# BNO085_IMU.net
KiCad netlist of a schematic drawn in Altium Designer
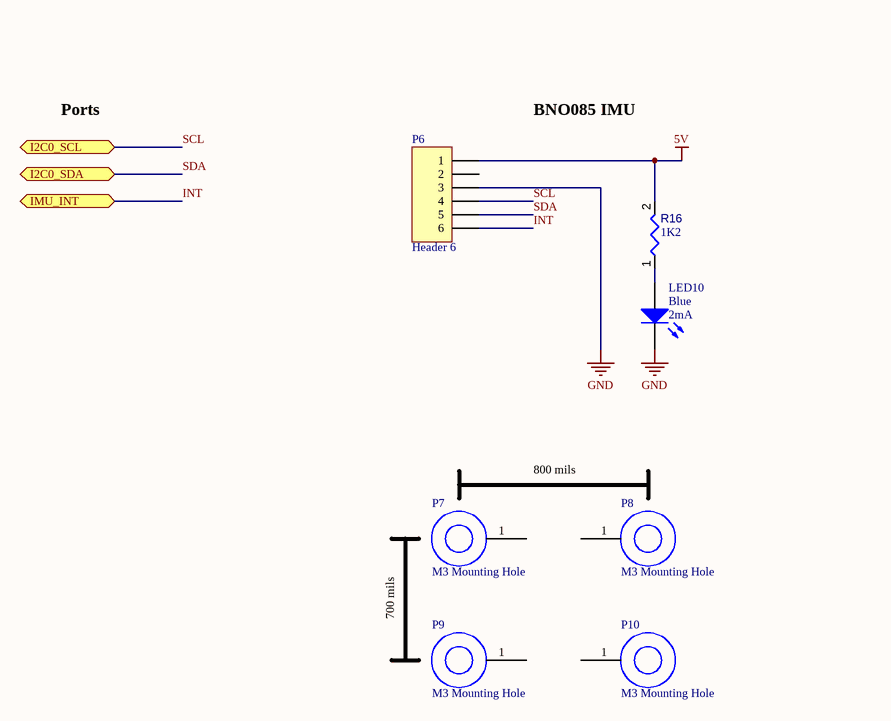
[diagram p0: BNO085_IMU.SchDoc]

(export (version "E")
  (design (tool "Eeschema 10.0.6"))
  (components
    (comp (ref "LED10")
      (value "Blue")
      (footprint "1206_A")
      (description "KPT-3216LVVBC-D -  LED, 3.2mm x 1.6mm, Blue, SMD, 2 mA, 2.65 V, 470 nm")
      (fields
        (field (name "MANUFACTURER") "Kingbright")
        (field (name "PARTNUMBER") "KPT-3216LVVBC-D")
        (field (name "IF") "2mA")
      )
      (libsource (lib "Altium Content Vault") (part "CMP-1426-00015-1"))
    )
    (comp (ref "P6")
      (value "Header 6")
      (footprint "HDR1X6")
      (description "Header, 6-Pin")
      (fields (field (name "PUBLISHER") "Altium Limited"))
      (libsource (lib "Miscellaneous Connectors") (part "Header 6"))
    )
    (comp (ref "P7")
      (value "M3 Mounting Hole")
      (footprint "M3 Mounting Hole")
      (description "M3 Mounting Hole, ID 2.73mm")
      (libsource (lib "CC3501_Misc_Symbols") (part "M3 Mounting Hole"))
    )
    (comp (ref "P8")
      (value "M3 Mounting Hole")
      (footprint "M3 Mounting Hole")
      (description "M3 Mounting Hole, ID 2.73mm")
      (libsource (lib "CC3501_Misc_Symbols") (part "M3 Mounting Hole"))
    )
    (comp (ref "P9")
      (value "M3 Mounting Hole")
      (footprint "M3 Mounting Hole")
      (description "M3 Mounting Hole, ID 2.73mm")
      (libsource (lib "CC3501_Misc_Symbols") (part "M3 Mounting Hole"))
    )
    (comp (ref "P10")
      (value "M3 Mounting Hole")
      (footprint "M3 Mounting Hole")
      (description "M3 Mounting Hole, ID 2.73mm")
      (libsource (lib "CC3501_Misc_Symbols") (part "M3 Mounting Hole"))
    )
    (comp (ref "R16")
      (value "1K2")
      (footprint "RESC0805(2012)_L")
      (description "1K2 0.125W 5% 0805 (2012 Metric)  SMD")
      (fields (field (name "POWER") "0.125W") (field (name "TOLERANCE") "5%"))
      (libsource (lib "James Cook University") (part "1KR5J"))
    )
  )
  (nets
    (net (code "1") (name "/INT") (class "Default")
      (node (ref "P6") (pin "6") (pinfunction "6_6") (pintype "passive"))
    )
    (net (code "2") (name "/SCL") (class "Default")
      (node (ref "P6") (pin "4") (pinfunction "4_4") (pintype "passive"))
    )
    (net (code "3") (name "/SDA") (class "Default")
      (node (ref "P6") (pin "5") (pinfunction "5_5") (pintype "passive"))
    )
    (net (code "4") (name "5V") (class "Default")
      (node (ref "P6") (pin "1") (pinfunction "1_1") (pintype "passive"))
      (node (ref "R16") (pin "2") (pinfunction "2_2") (pintype "passive"))
    )
    (net (code "5") (name "GND") (class "Default")
      (node (ref "LED10") (pin "1") (pinfunction "K_1") (pintype "passive"))
      (node (ref "P6") (pin "3") (pinfunction "3_3") (pintype "passive"))
    )
    (net (code "6") (name "Net-(LED10-A)") (class "Default")
      (node (ref "LED10") (pin "2") (pinfunction "A_2") (pintype "passive"))
      (node (ref "R16") (pin "1") (pinfunction "1_1") (pintype "passive"))
    )
    (net (code "7") (name "unconnected-(P6-Pad2)") (class "Default")
      (node (ref "P6") (pin "2") (pinfunction "2_2") (pintype "passive"))
    )
    (net (code "8") (name "unconnected-(P7-Pad1)") (class "Default")
      (node (ref "P7") (pin "1") (pintype "power_in"))
    )
    (net (code "9") (name "unconnected-(P8-Pad1)") (class "Default")
      (node (ref "P8") (pin "1") (pintype "power_in"))
    )
    (net (code "10") (name "unconnected-(P9-Pad1)") (class "Default")
      (node (ref "P9") (pin "1") (pintype "power_in"))
    )
    (net (code "11") (name "unconnected-(P10-Pad1)") (class "Default")
      (node (ref "P10") (pin "1") (pintype "power_in"))
    )
  )
)
